# Driver.net
KiCad netlist of a schematic drawn in Altium Designer
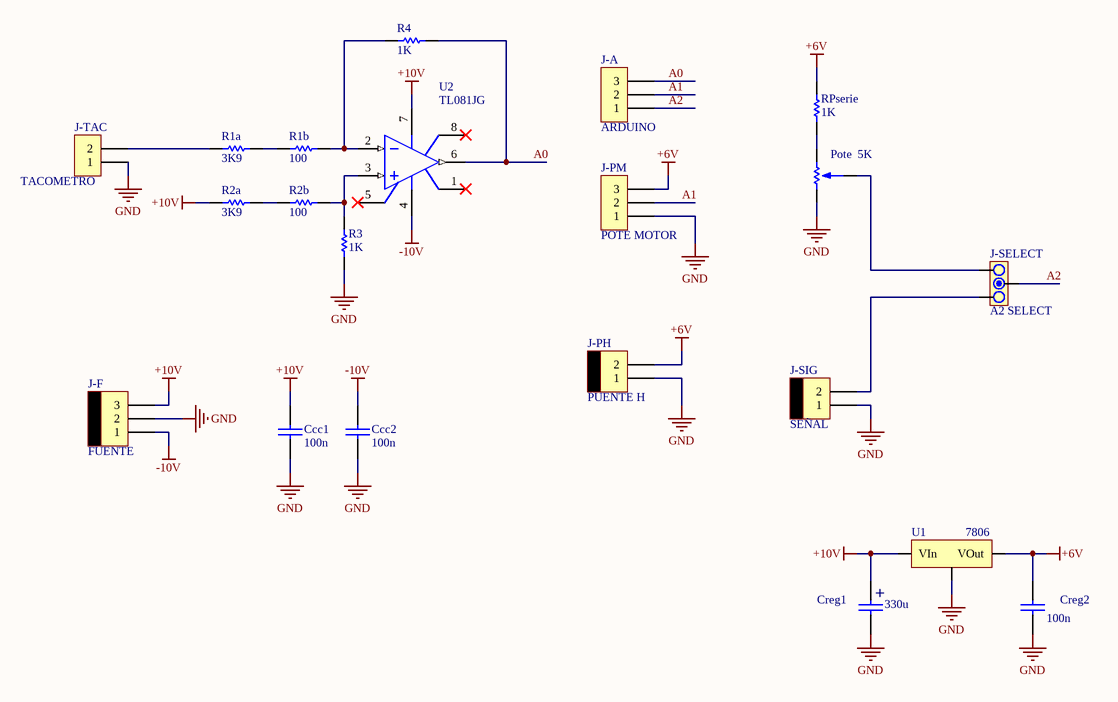
[diagram p0: Driver.SchDoc]

(export (version "E")
  (design (tool "Eeschema 10.0.6"))
  (components
    (comp (ref "Ccc1") (value "100n") (footprint "CAP200") (libsource (lib "LIBEBAL") (part "CAP")))
    (comp (ref "Ccc2") (value "100n") (footprint "CAP100") (libsource (lib "LIBEBAL") (part "CAP")))
    (comp (ref "Creg1") (value "330u") (footprint "CAP200RP") (libsource (lib "LIBEBAL") (part "CAPPOL")))
    (comp (ref "Creg2") (value "100n") (footprint "CAP100") (libsource (lib "LIBEBAL") (part "CAP")))
    (comp (ref "J-A") (value "ARDUINO") (footprint "SIP3") (libsource (lib "LIBEBAL") (part "CON3")))
    (comp (ref "J-F") (value "FUENTE") (footprint "MOLEX3") (libsource (lib "LIBEBAL") (part "MOLEX3")))
    (comp (ref "J-PH") (value "PUENTE H") (footprint "MOLEX2") (libsource (lib "LIBEBAL") (part "MOLEX2")))
    (comp (ref "J-PM")
      (value "POTE MOTOR")
      (footprint "BORNERA3")
      (libsource (lib "LIBEBAL") (part "BORNERA 3"))
    )
    (comp (ref "J-SELECT")
      (value "A2 SELECT")
      (footprint "JUMPER3")
      (libsource (lib "LIBEBAL") (part "JUMPER3"))
    )
    (comp (ref "J-SIG") (value "SEÑAL") (footprint "MOLEX2") (libsource (lib "LIBEBAL") (part "MOLEX2")))
    (comp (ref "J-TAC")
      (value "TACOMETRO")
      (footprint "BORNERA2")
      (libsource (lib "LIBEBAL") (part "BORNERA 2"))
    )
    (comp (ref "Pote")
      (value "5K")
      (footprint "POTENCIOMETRO")
      (libsource (lib "LIBEBAL") (part "POTENCIOMETRO"))
    )
    (comp (ref "R1a") (value "3K9") (footprint "RES300") (libsource (lib "LIBEBAL") (part "RES")))
    (comp (ref "R1b") (value "100") (footprint "RES300") (libsource (lib "LIBEBAL") (part "RES")))
    (comp (ref "R2a") (value "3K9") (footprint "RES300") (libsource (lib "LIBEBAL") (part "RES")))
    (comp (ref "R2b") (value "100") (footprint "RES300") (libsource (lib "LIBEBAL") (part "RES")))
    (comp (ref "R3") (value "1K") (footprint "RES300") (libsource (lib "LIBEBAL") (part "RES")))
    (comp (ref "R4") (value "1K") (footprint "RES300") (libsource (lib "LIBEBAL") (part "RES")))
    (comp (ref "RPserie") (value "1K") (footprint "RES300") (libsource (lib "LIBEBAL") (part "RES")))
    (comp (ref "U1")
      (value "7806")
      (footprint "TO-220 V")
      (description "REGULDOR POSITIVO")
      (libsource (lib "LIBEBAL") (part "78XX"))
    )
    (comp (ref "U2")
      (value "TL081JG")
      (footprint "JG008")
      (description "JFET-Input Operational Amplifier")
      (fields (field (name "PUBLISHER") "Altium Limited"))
      (libsource (lib "TI Operational Amplifier") (part "TL081JG"))
    )
  )
  (nets
    (net (code "1") (name "+6V") (class "Default")
      (node (ref "Creg2") (pin "1") (pinfunction "1_1") (pintype "passive"))
      (node (ref "J-PH") (pin "2") (pinfunction "2_2") (pintype "passive"))
      (node (ref "J-PM") (pin "3") (pinfunction "3_3") (pintype "passive"))
      (node (ref "RPserie") (pin "2") (pinfunction "2_2") (pintype "passive"))
      (node (ref "U1") (pin "3") (pinfunction "VOut_3") (pintype "passive"))
    )
    (net (code "2") (name "+10V") (class "Default")
      (node (ref "Ccc1") (pin "1") (pinfunction "1_1") (pintype "passive"))
      (node (ref "Creg1") (pin "1") (pinfunction "1_1") (pintype "passive"))
      (node (ref "J-F") (pin "3") (pinfunction "3_3") (pintype "passive"))
      (node (ref "R2a") (pin "1") (pinfunction "1_1") (pintype "passive"))
      (node (ref "U1") (pin "1") (pinfunction "VIn_1") (pintype "passive"))
      (node (ref "U2") (pin "7") (pinfunction "V+_7") (pintype "power_in"))
    )
    (net (code "3") (name "-10V") (class "Default")
      (node (ref "Ccc2") (pin "1") (pinfunction "1_1") (pintype "passive"))
      (node (ref "J-F") (pin "1") (pinfunction "1_1") (pintype "passive"))
      (node (ref "U2") (pin "4") (pinfunction "V-_4") (pintype "power_in"))
    )
    (net (code "4") (name "/A0") (class "Default")
      (node (ref "J-A") (pin "3") (pinfunction "3_3") (pintype "passive"))
      (node (ref "R4") (pin "2") (pinfunction "2_2") (pintype "passive"))
      (node (ref "U2") (pin "6") (pinfunction "OUT_6") (pintype "output"))
    )
    (net (code "5") (name "/A1") (class "Default")
      (node (ref "J-A") (pin "2") (pinfunction "2_2") (pintype "passive"))
      (node (ref "J-PM") (pin "2") (pinfunction "2_2") (pintype "passive"))
    )
    (net (code "6") (name "/A2") (class "Default")
      (node (ref "J-A") (pin "1") (pinfunction "1_1") (pintype "passive"))
      (node (ref "J-SELECT") (pin "2") (pinfunction "2_2") (pintype "passive"))
    )
    (net (code "7") (name "GND") (class "Default")
      (node (ref "Ccc1") (pin "2") (pinfunction "2_2") (pintype "passive"))
      (node (ref "Ccc2") (pin "2") (pinfunction "2_2") (pintype "passive"))
      (node (ref "Creg1") (pin "2") (pinfunction "2_2") (pintype "passive"))
      (node (ref "Creg2") (pin "2") (pinfunction "2_2") (pintype "passive"))
      (node (ref "J-F") (pin "2") (pinfunction "2_2") (pintype "passive"))
      (node (ref "J-PH") (pin "1") (pinfunction "1_1") (pintype "passive"))
      (node (ref "J-PM") (pin "1") (pinfunction "1_1") (pintype "passive"))
      (node (ref "J-SIG") (pin "1") (pinfunction "1_1") (pintype "passive"))
      (node (ref "J-TAC") (pin "1") (pinfunction "1_1") (pintype "passive"))
      (node (ref "Pote") (pin "3") (pinfunction "3_3") (pintype "passive"))
      (node (ref "R3") (pin "1") (pinfunction "1_1") (pintype "passive"))
      (node (ref "U1") (pin "2") (pinfunction "GND_2") (pintype "passive"))
    )
    (net (code "8") (name "Net-(J-SELECT-Pad1)") (class "Default")
      (node (ref "J-SELECT") (pin "1") (pinfunction "1_1") (pintype "passive"))
      (node (ref "J-SIG") (pin "2") (pinfunction "2_2") (pintype "passive"))
    )
    (net (code "9") (name "Net-(J-SELECT-Pad3)") (class "Default")
      (node (ref "J-SELECT") (pin "3") (pinfunction "3_3") (pintype "passive"))
      (node (ref "Pote") (pin "2") (pinfunction "2_2") (pintype "passive"))
    )
    (net (code "10") (name "Net-(J-TAC-Pad2)") (class "Default")
      (node (ref "J-TAC") (pin "2") (pinfunction "2_2") (pintype "passive"))
      (node (ref "R1a") (pin "1") (pinfunction "1_1") (pintype "passive"))
    )
    (net (code "11") (name "Net-(Pote-Pad1)") (class "Default")
      (node (ref "Pote") (pin "1") (pinfunction "1_1") (pintype "passive"))
      (node (ref "RPserie") (pin "1") (pinfunction "1_1") (pintype "passive"))
    )
    (net (code "12") (name "Net-(R1a-Pad2)") (class "Default")
      (node (ref "R1a") (pin "2") (pinfunction "2_2") (pintype "passive"))
      (node (ref "R1b") (pin "1") (pinfunction "1_1") (pintype "passive"))
    )
    (net (code "13") (name "Net-(R2a-Pad2)") (class "Default")
      (node (ref "R2a") (pin "2") (pinfunction "2_2") (pintype "passive"))
      (node (ref "R2b") (pin "1") (pinfunction "1_1") (pintype "passive"))
    )
    (net (code "14") (name "Net-(U2-IN+)") (class "Default")
      (node (ref "R2b") (pin "2") (pinfunction "2_2") (pintype "passive"))
      (node (ref "R3") (pin "2") (pinfunction "2_2") (pintype "passive"))
      (node (ref "U2") (pin "3") (pinfunction "IN+_3") (pintype "input"))
    )
    (net (code "15") (name "Net-(U2-IN-)") (class "Default")
      (node (ref "R1b") (pin "2") (pinfunction "2_2") (pintype "passive"))
      (node (ref "R4") (pin "1") (pinfunction "1_1") (pintype "passive"))
      (node (ref "U2") (pin "2") (pinfunction "IN-_2") (pintype "input"))
    )
    (net (code "16") (name "unconnected-(U2-NC-Pad8)") (class "Default")
      (node (ref "U2") (pin "8") (pinfunction "NC_8") (pintype "passive+no_connect"))
    )
    (net (code "17") (name "unconnected-(U2-OS_TRIM-Pad1)") (class "Default")
      (node (ref "U2") (pin "1") (pinfunction "OS_TRIM_1") (pintype "passive+no_connect"))
    )
    (net (code "18") (name "unconnected-(U2-OS_TRIM-Pad5)") (class "Default")
      (node (ref "U2") (pin "5") (pinfunction "OS_TRIM_5") (pintype "passive+no_connect"))
    )
  )
)
